# monitor_riser.net
KiCad netlist of a schematic drawn in EAGLE
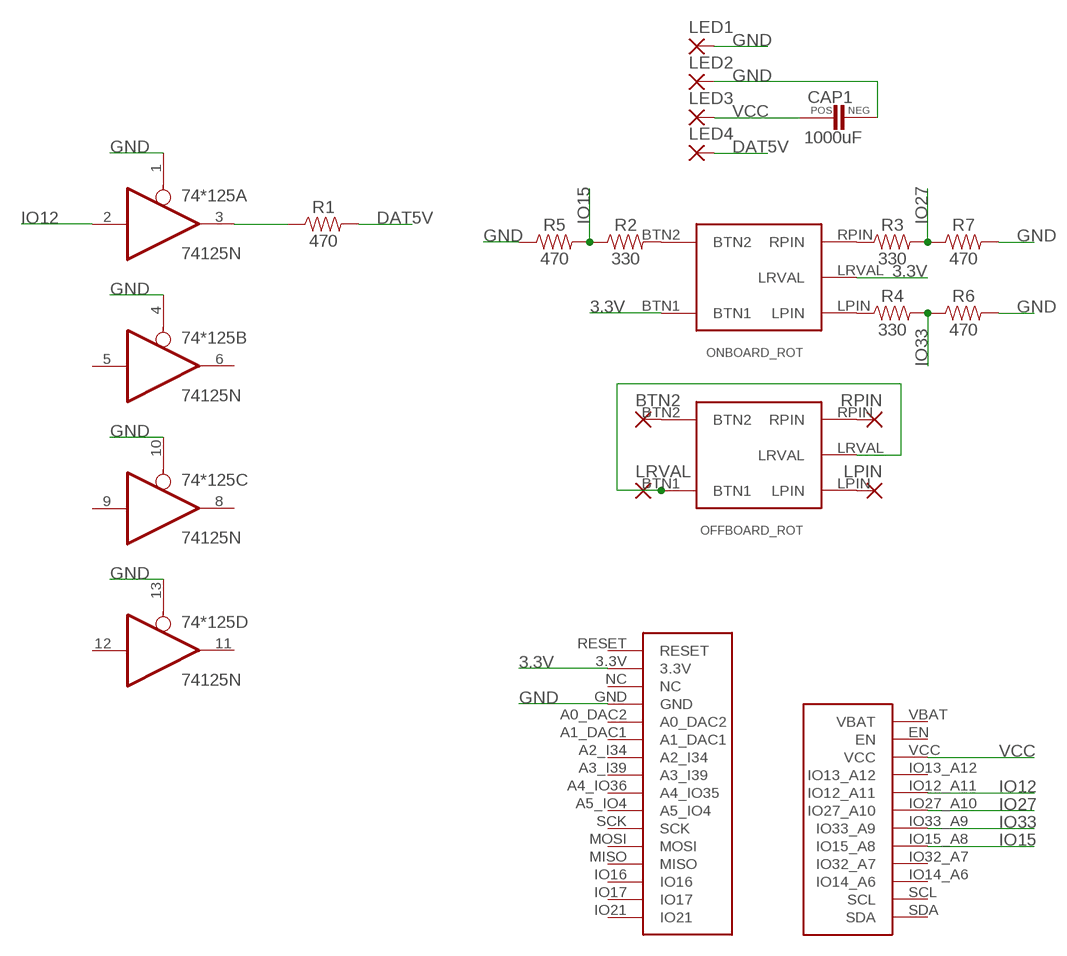
[diagram p0: schematic, sheet 1]

(export (version "E")
  (design (tool "Eeschema 10.0.6"))
  (components
    (comp (ref "74*125")
      (value "74125N")
      (footprint "eagle-import:DIL14")
      (libsource (lib "eagle-import") (part "74125N"))
    )
    (comp (ref "BTN2")
      (value "1,6/0,9")
      (footprint "eagle-import:1,6_0,9")
      (libsource (lib "eagle-import") (part "1,6/0,9"))
    )
    (comp (ref "CAP1")
      (value "1000uF")
      (footprint "eagle-import:CAP1000UF_0807_0304")
      (libsource (lib "eagle-import") (part "CAP1000UF_0807_0304"))
    )
    (comp (ref "LED1")
      (value "1,6/0,9")
      (footprint "eagle-import:1,6_0,9")
      (libsource (lib "eagle-import") (part "1,6/0,9"))
    )
    (comp (ref "LED2")
      (value "1,6/0,9")
      (footprint "eagle-import:1,6_0,9")
      (libsource (lib "eagle-import") (part "1,6/0,9"))
    )
    (comp (ref "LED3")
      (value "1,6/0,9")
      (footprint "eagle-import:1,6_0,9")
      (libsource (lib "eagle-import") (part "1,6/0,9"))
    )
    (comp (ref "LED4")
      (value "1,6/0,9")
      (footprint "eagle-import:1,6_0,9")
      (libsource (lib "eagle-import") (part "1,6/0,9"))
    )
    (comp (ref "LPIN")
      (value "1,6/0,9")
      (footprint "eagle-import:1,6_0,9")
      (libsource (lib "eagle-import") (part "1,6/0,9"))
    )
    (comp (ref "LRVAL")
      (value "1,6/0,9")
      (footprint "eagle-import:1,6_0,9")
      (libsource (lib "eagle-import") (part "1,6/0,9"))
    )
    (comp (ref "OFFBOARD_ROT")
      (value "ROTARYENCODER")
      (footprint "eagle-import:ROTARYENCODER")
      (libsource (lib "eagle-import") (part "ROTARYENCODER"))
    )
    (comp (ref "ONBOARD_ROT")
      (value "ROTARYENCODER")
      (footprint "eagle-import:ROTARYENCODER")
      (libsource (lib "eagle-import") (part "ROTARYENCODER"))
    )
    (comp (ref "R1")
      (value "470")
      (footprint "eagle-import:AXIAL-0.3")
      (libsource (lib "eagle-import") (part "RESISTORAXIAL-0.3"))
    )
    (comp (ref "R2")
      (value "330")
      (footprint "eagle-import:AXIAL-0.3")
      (libsource (lib "eagle-import") (part "RESISTORAXIAL-0.3"))
    )
    (comp (ref "R3")
      (value "330")
      (footprint "eagle-import:AXIAL-0.3")
      (libsource (lib "eagle-import") (part "RESISTORAXIAL-0.3"))
    )
    (comp (ref "R4")
      (value "330")
      (footprint "eagle-import:AXIAL-0.3")
      (libsource (lib "eagle-import") (part "RESISTORAXIAL-0.3"))
    )
    (comp (ref "R5")
      (value "470")
      (footprint "eagle-import:AXIAL-0.3")
      (libsource (lib "eagle-import") (part "RESISTORAXIAL-0.3"))
    )
    (comp (ref "R6")
      (value "470")
      (footprint "eagle-import:AXIAL-0.3")
      (libsource (lib "eagle-import") (part "RESISTORAXIAL-0.3"))
    )
    (comp (ref "R7")
      (value "470")
      (footprint "eagle-import:AXIAL-0.3")
      (libsource (lib "eagle-import") (part "RESISTORAXIAL-0.3"))
    )
    (comp (ref "RPIN")
      (value "1,6/0,9")
      (footprint "eagle-import:1,6_0,9")
      (libsource (lib "eagle-import") (part "1,6/0,9"))
    )
    (comp (ref "U$1")
      (value "FEATHER32")
      (footprint "eagle-import:FEATHER32")
      (libsource (lib "eagle-import") (part "FEATHER32"))
    )
  )
  (nets
    (net (code "1") (name "/3.3V") (class "Default")
      (node (ref "ONBOARD_ROT") (pin "BTN1") (pinfunction "BTN1_BTN1") (pintype "bidirectional"))
      (node (ref "ONBOARD_ROT") (pin "LRVAL") (pinfunction "LRVAL_LRVAL") (pintype "bidirectional"))
      (node (ref "U$1") (pin "3.3V") (pinfunction "3.3V_3.3V") (pintype "bidirectional"))
    )
    (net (code "2") (name "/DAT5V") (class "Default")
      (node (ref "LED4") (pin "1") (pinfunction "P_1") (pintype "passive"))
      (node (ref "R1") (pin "P$2") (pinfunction "2_P$2") (pintype "passive"))
    )
    (net (code "3") (name "/GND") (class "Default")
      (node (ref "74*125") (pin "1") (pinfunction "OE_1") (pintype "input"))
      (node (ref "74*125") (pin "10") (pinfunction "OE_10") (pintype "input"))
      (node (ref "74*125") (pin "13") (pinfunction "OE_13") (pintype "input"))
      (node (ref "74*125") (pin "4") (pinfunction "OE_4") (pintype "input"))
      (node (ref "CAP1") (pin "NEG") (pinfunction "NEG_NEG") (pintype "bidirectional"))
      (node (ref "LED1") (pin "1") (pinfunction "P_1") (pintype "passive"))
      (node (ref "LED2") (pin "1") (pinfunction "P_1") (pintype "passive"))
      (node (ref "R5") (pin "P$1") (pinfunction "1_P$1") (pintype "passive"))
      (node (ref "R6") (pin "P$2") (pinfunction "2_P$2") (pintype "passive"))
      (node (ref "R7") (pin "P$2") (pinfunction "2_P$2") (pintype "passive"))
      (node (ref "U$1") (pin "GND") (pinfunction "GND_GND") (pintype "bidirectional"))
    )
    (net (code "4") (name "/IO12") (class "Default")
      (node (ref "74*125") (pin "2") (pinfunction "I_2") (pintype "input"))
      (node (ref "U$1") (pin "IO12_A11") (pinfunction "IO12_A11_IO12_A11") (pintype "bidirectional"))
    )
    (net (code "5") (name "/IO15") (class "Default")
      (node (ref "R2") (pin "P$1") (pinfunction "1_P$1") (pintype "passive"))
      (node (ref "R5") (pin "P$2") (pinfunction "2_P$2") (pintype "passive"))
      (node (ref "U$1") (pin "IO15_A8") (pinfunction "IO15_A8_IO15_A8") (pintype "bidirectional"))
    )
    (net (code "6") (name "/IO27") (class "Default")
      (node (ref "R3") (pin "P$2") (pinfunction "2_P$2") (pintype "passive"))
      (node (ref "R7") (pin "P$1") (pinfunction "1_P$1") (pintype "passive"))
      (node (ref "U$1") (pin "IO27_A10") (pinfunction "IO27_A10_IO27_A10") (pintype "bidirectional"))
    )
    (net (code "7") (name "/IO33") (class "Default")
      (node (ref "R4") (pin "P$2") (pinfunction "2_P$2") (pintype "passive"))
      (node (ref "R6") (pin "P$1") (pinfunction "1_P$1") (pintype "passive"))
      (node (ref "U$1") (pin "IO33_A9") (pinfunction "IO33_A9_IO33_A9") (pintype "bidirectional"))
    )
    (net (code "8") (name "/VCC") (class "Default")
      (node (ref "CAP1") (pin "POS") (pinfunction "POS_POS") (pintype "bidirectional"))
      (node (ref "LED3") (pin "1") (pinfunction "P_1") (pintype "passive"))
      (node (ref "U$1") (pin "VCC") (pinfunction "VCC_VCC") (pintype "bidirectional"))
    )
    (net (code "9") (name "Net-(74*125A-O)") (class "Default")
      (node (ref "74*125") (pin "3") (pinfunction "O_3") (pintype "tri_state"))
      (node (ref "R1") (pin "P$1") (pinfunction "1_P$1") (pintype "passive"))
    )
    (net (code "10") (name "Net-(BTN2-P)") (class "Default")
      (node (ref "BTN2") (pin "1") (pinfunction "P_1") (pintype "passive"))
      (node (ref "OFFBOARD_ROT") (pin "BTN2") (pinfunction "BTN2_BTN2") (pintype "bidirectional"))
    )
    (net (code "11") (name "Net-(LPIN-P)") (class "Default")
      (node (ref "LPIN") (pin "1") (pinfunction "P_1") (pintype "passive"))
      (node (ref "OFFBOARD_ROT") (pin "LPIN") (pinfunction "LPIN_LPIN") (pintype "bidirectional"))
    )
    (net (code "12") (name "Net-(LRVAL-P)") (class "Default")
      (node (ref "LRVAL") (pin "1") (pinfunction "P_1") (pintype "passive"))
      (node (ref "OFFBOARD_ROT") (pin "BTN1") (pinfunction "BTN1_BTN1") (pintype "bidirectional"))
      (node (ref "OFFBOARD_ROT") (pin "LRVAL") (pinfunction "LRVAL_LRVAL") (pintype "bidirectional"))
    )
    (net (code "13") (name "Net-(R2-2)") (class "Default")
      (node (ref "ONBOARD_ROT") (pin "BTN2") (pinfunction "BTN2_BTN2") (pintype "bidirectional"))
      (node (ref "R2") (pin "P$2") (pinfunction "2_P$2") (pintype "passive"))
    )
    (net (code "14") (name "Net-(R3-1)") (class "Default")
      (node (ref "ONBOARD_ROT") (pin "RPIN") (pinfunction "RPIN_RPIN") (pintype "bidirectional"))
      (node (ref "R3") (pin "P$1") (pinfunction "1_P$1") (pintype "passive"))
    )
    (net (code "15") (name "Net-(R4-1)") (class "Default")
      (node (ref "ONBOARD_ROT") (pin "LPIN") (pinfunction "LPIN_LPIN") (pintype "bidirectional"))
      (node (ref "R4") (pin "P$1") (pinfunction "1_P$1") (pintype "passive"))
    )
    (net (code "16") (name "Net-(RPIN-P)") (class "Default")
      (node (ref "OFFBOARD_ROT") (pin "RPIN") (pinfunction "RPIN_RPIN") (pintype "bidirectional"))
      (node (ref "RPIN") (pin "1") (pinfunction "P_1") (pintype "passive"))
    )
    (net (code "17") (name "unconnected-(74*125B-I-Pad5)") (class "Default")
      (node (ref "74*125") (pin "5") (pinfunction "I_5") (pintype "input"))
    )
    (net (code "18") (name "unconnected-(74*125B-O-Pad6)") (class "Default")
      (node (ref "74*125") (pin "6") (pinfunction "O_6") (pintype "tri_state"))
    )
    (net (code "19") (name "unconnected-(74*125C-I-Pad9)") (class "Default")
      (node (ref "74*125") (pin "9") (pinfunction "I_9") (pintype "input"))
    )
    (net (code "20") (name "unconnected-(74*125C-O-Pad8)") (class "Default")
      (node (ref "74*125") (pin "8") (pinfunction "O_8") (pintype "tri_state"))
    )
    (net (code "21") (name "unconnected-(74*125D-I-Pad12)") (class "Default")
      (node (ref "74*125") (pin "12") (pinfunction "I_12") (pintype "input"))
    )
    (net (code "22") (name "unconnected-(74*125D-O-Pad11)") (class "Default")
      (node (ref "74*125") (pin "11") (pinfunction "O_11") (pintype "tri_state"))
    )
    (net (code "23") (name "unconnected-(U$1-A4_IO35-PadA4_IO36)") (class "Default")
      (node (ref "U$1") (pin "A4_IO36") (pinfunction "A4_IO35_A4_IO36") (pintype "bidirectional"))
    )
    (net (code "24") (name "unconnected-(U$1-PadA0_DAC2)") (class "Default")
      (node (ref "U$1") (pin "A0_DAC2") (pinfunction "A0_DAC2_A0_DAC2") (pintype "bidirectional"))
    )
    (net (code "25") (name "unconnected-(U$1-PadA1_DAC1)") (class "Default")
      (node (ref "U$1") (pin "A1_DAC1") (pinfunction "A1_DAC1_A1_DAC1") (pintype "bidirectional"))
    )
    (net (code "26") (name "unconnected-(U$1-PadA2_I34)") (class "Default")
      (node (ref "U$1") (pin "A2_I34") (pinfunction "A2_I34_A2_I34") (pintype "bidirectional"))
    )
    (net (code "27") (name "unconnected-(U$1-PadA3_I39)") (class "Default")
      (node (ref "U$1") (pin "A3_I39") (pinfunction "A3_I39_A3_I39") (pintype "bidirectional"))
    )
    (net (code "28") (name "unconnected-(U$1-PadA5_IO4)") (class "Default")
      (node (ref "U$1") (pin "A5_IO4") (pinfunction "A5_IO4_A5_IO4") (pintype "bidirectional"))
    )
    (net (code "29") (name "unconnected-(U$1-PadEN)") (class "Default")
      (node (ref "U$1") (pin "EN") (pinfunction "EN_EN") (pintype "bidirectional"))
    )
    (net (code "30") (name "unconnected-(U$1-PadIO13_A12)") (class "Default")
      (node (ref "U$1") (pin "IO13_A12") (pinfunction "IO13_A12_IO13_A12") (pintype "bidirectional"))
    )
    (net (code "31") (name "unconnected-(U$1-PadIO14_A6)") (class "Default")
      (node (ref "U$1") (pin "IO14_A6") (pinfunction "IO14_A6_IO14_A6") (pintype "bidirectional"))
    )
    (net (code "32") (name "unconnected-(U$1-PadIO16)") (class "Default")
      (node (ref "U$1") (pin "IO16") (pinfunction "IO16_IO16") (pintype "bidirectional"))
    )
    (net (code "33") (name "unconnected-(U$1-PadIO17)") (class "Default")
      (node (ref "U$1") (pin "IO17") (pinfunction "IO17_IO17") (pintype "bidirectional"))
    )
    (net (code "34") (name "unconnected-(U$1-PadIO21)") (class "Default")
      (node (ref "U$1") (pin "IO21") (pinfunction "IO21_IO21") (pintype "bidirectional"))
    )
    (net (code "35") (name "unconnected-(U$1-PadIO32_A7)") (class "Default")
      (node (ref "U$1") (pin "IO32_A7") (pinfunction "IO32_A7_IO32_A7") (pintype "bidirectional"))
    )
    (net (code "36") (name "unconnected-(U$1-PadMISO)") (class "Default")
      (node (ref "U$1") (pin "MISO") (pinfunction "MISO_MISO") (pintype "bidirectional"))
    )
    (net (code "37") (name "unconnected-(U$1-PadMOSI)") (class "Default")
      (node (ref "U$1") (pin "MOSI") (pinfunction "MOSI_MOSI") (pintype "bidirectional"))
    )
    (net (code "38") (name "unconnected-(U$1-PadNC)") (class "Default")
      (node (ref "U$1") (pin "NC") (pinfunction "NC_NC") (pintype "bidirectional"))
    )
    (net (code "39") (name "unconnected-(U$1-PadRESET)") (class "Default")
      (node (ref "U$1") (pin "RESET") (pinfunction "RESET_RESET") (pintype "bidirectional"))
    )
    (net (code "40") (name "unconnected-(U$1-PadSCK)") (class "Default")
      (node (ref "U$1") (pin "SCK") (pinfunction "SCK_SCK") (pintype "bidirectional"))
    )
    (net (code "41") (name "unconnected-(U$1-PadSCL)") (class "Default")
      (node (ref "U$1") (pin "SCL") (pinfunction "SCL_SCL") (pintype "bidirectional"))
    )
    (net (code "42") (name "unconnected-(U$1-PadSDA)") (class "Default")
      (node (ref "U$1") (pin "SDA") (pinfunction "SDA_SDA") (pintype "bidirectional"))
    )
    (net (code "43") (name "unconnected-(U$1-PadVBAT)") (class "Default")
      (node (ref "U$1") (pin "VBAT") (pinfunction "VBAT_VBAT") (pintype "bidirectional"))
    )
  )
)
